# TIDA-01349_Inverter_VISense.net
KiCad netlist of a schematic drawn in Altium Designer
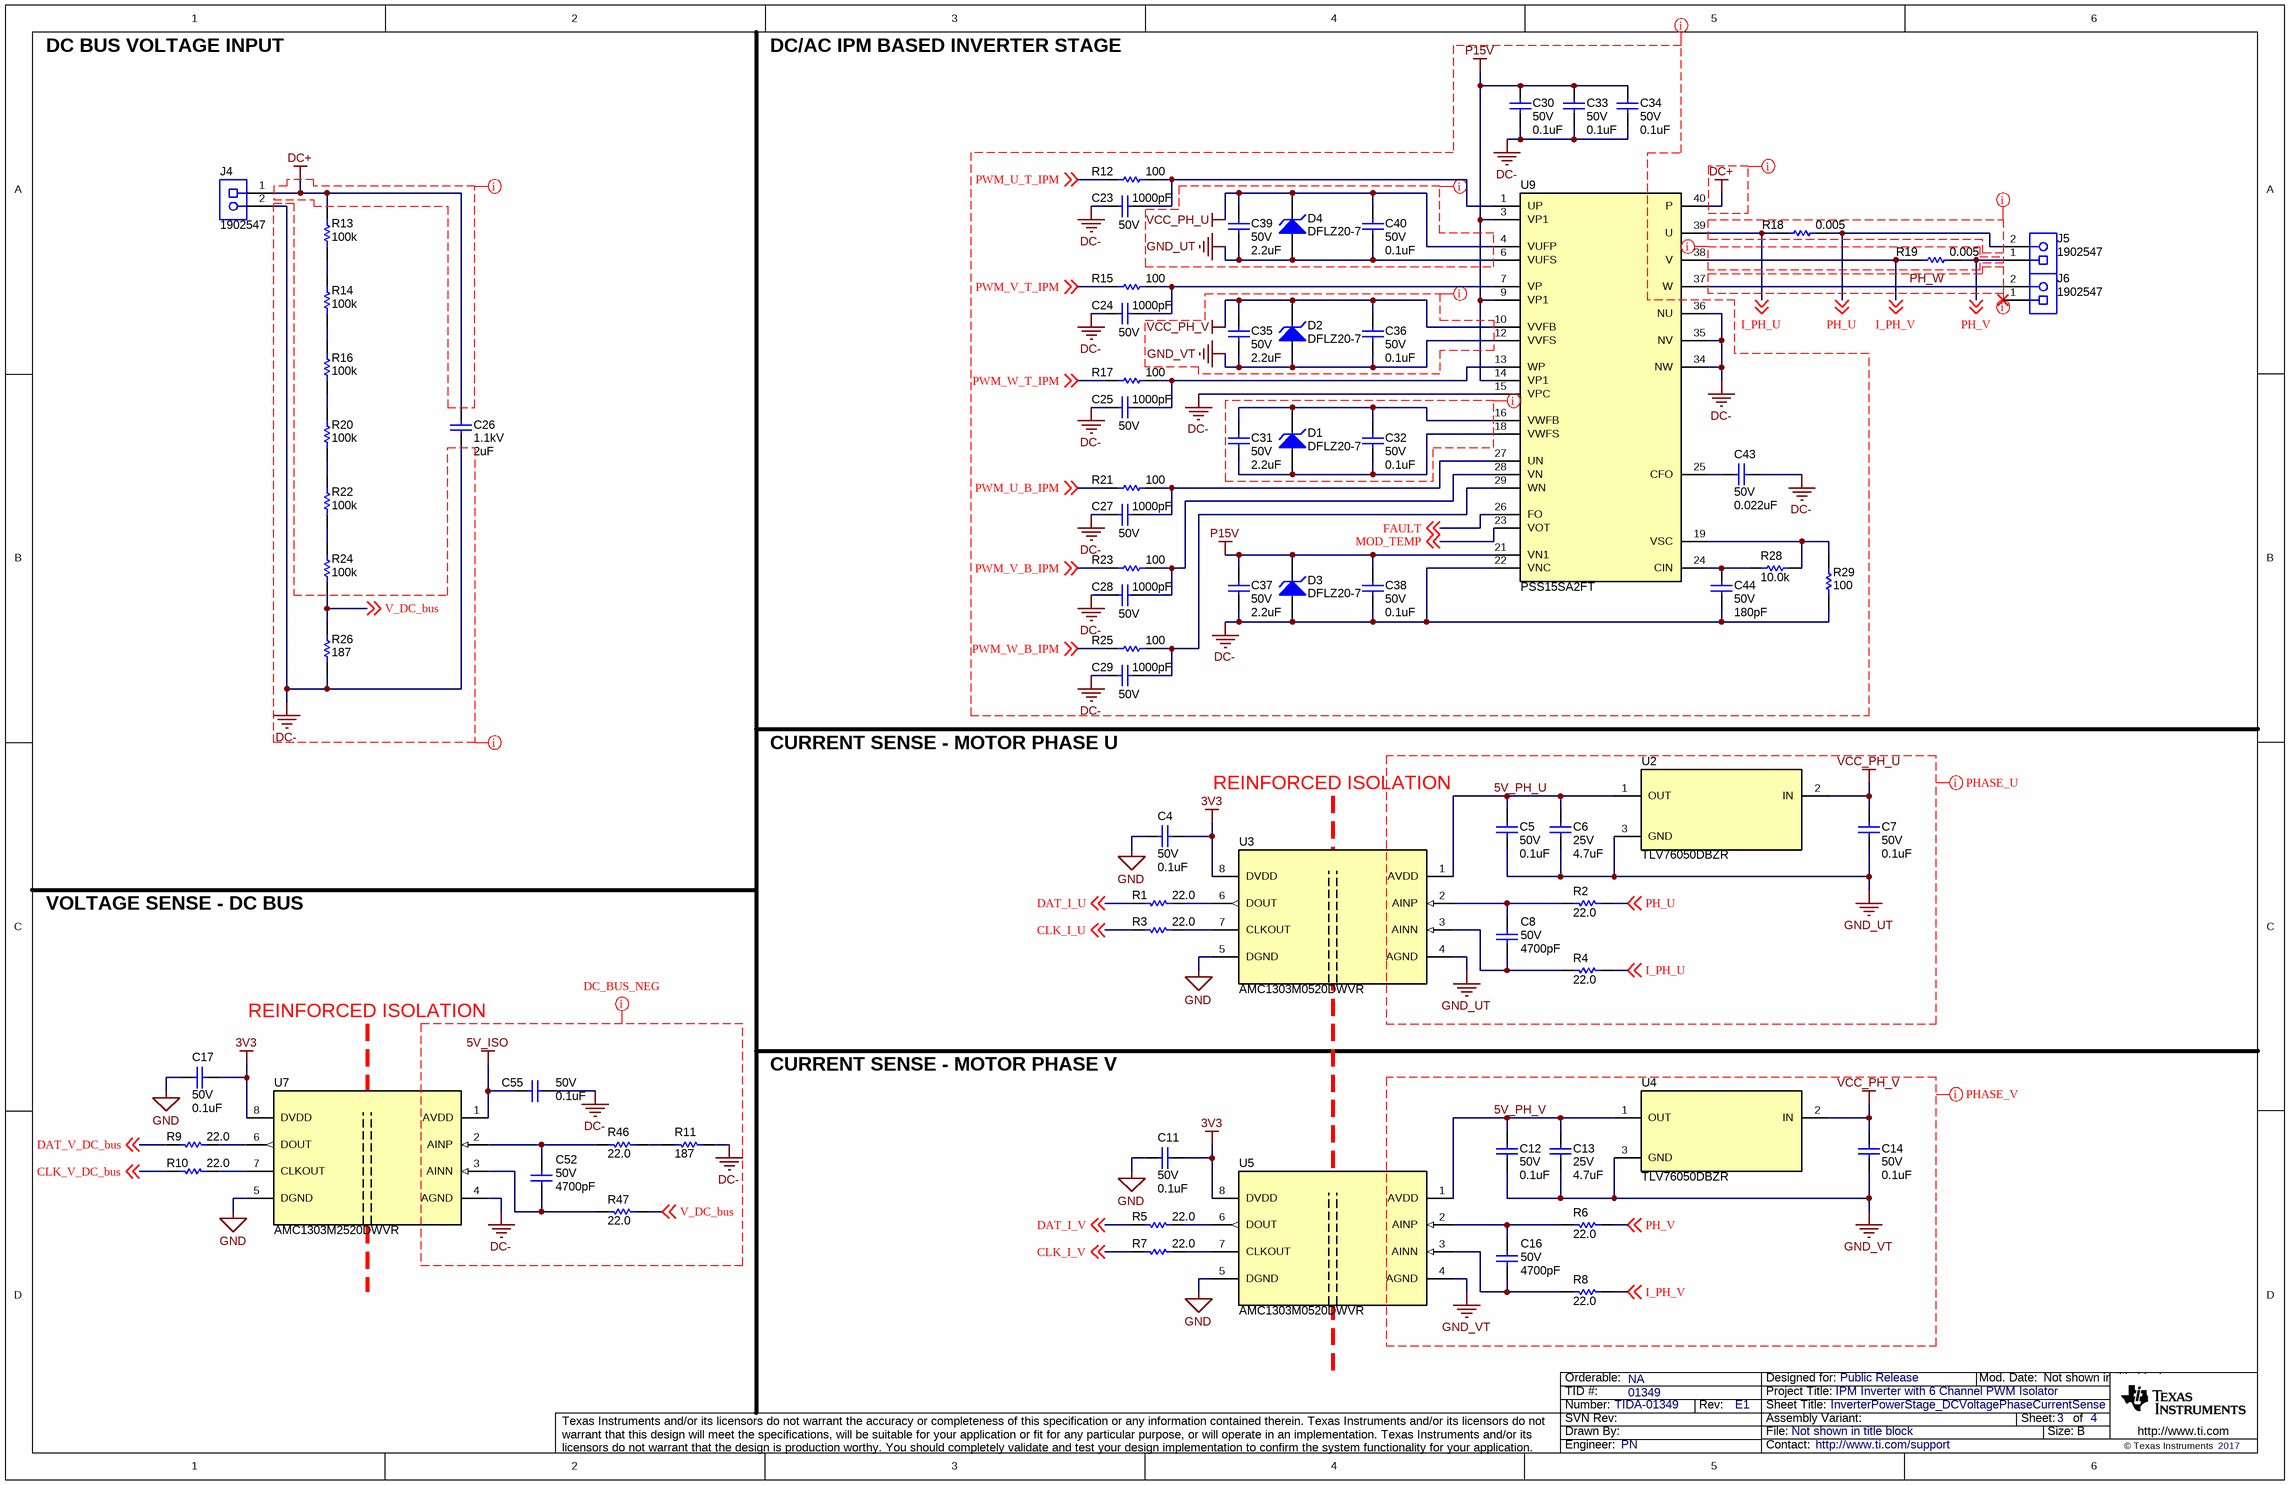
[diagram p0: TIDA-01349_Inverter_VISense.SchDoc]

(export (version "E")
  (design (tool "Eeschema 10.0.6"))
  (components
    (comp (ref "C4")
      (value "C0603C104K5RACTU")
      (footprint "0603")
      (description "CAP, CERM, 0.1 uF, 50 V, +/- 10%, X7R, 0603")
      (fields
        (field (name "MANUFACTURER") "Kemet")
        (field (name "VDC_V") "50V")
        (field (name "VALUEDISPLAYED") "0.1uF")
        (field (name "PUBLISHER") "Texas Instruments")
      )
      (libsource (lib "Altium Vault - TI") (part "Capacitor"))
    )
    (comp (ref "C5")
      (value "C1206C104K5RACTU")
      (footprint "1206")
      (description "CAP, CERM, 0.1 uF, 50 V, +/- 10%, X7R, 1206")
      (fields
        (field (name "MANUFACTURER") "Kemet")
        (field (name "VDC_V") "50V")
        (field (name "VALUEDISPLAYED") "0.1uF")
        (field (name "PUBLISHER") "Texas Instruments")
      )
      (libsource (lib "Altium Vault - TI") (part "Capacitor"))
    )
    (comp (ref "C6")
      (value "C2012X7R1E475K125AB")
      (footprint "0805_HV")
      (description "CAP, CERM, 4.7 uF, 25 V, +/- 10%, X7R, 0805")
      (fields
        (field (name "MANUFACTURER") "TDK")
        (field (name "VDC_V") "25V")
        (field (name "VALUEDISPLAYED") "4.7uF")
        (field (name "PUBLISHER") "Texas Instruments")
      )
      (libsource (lib "Altium Vault - TI") (part "Capacitor"))
    )
    (comp (ref "C7")
      (value "C0603C104K5RACTU")
      (footprint "0603")
      (description "CAP, CERM, 0.1 uF, 50 V, +/- 10%, X7R, 0603")
      (fields
        (field (name "MANUFACTURER") "Kemet")
        (field (name "VDC_V") "50V")
        (field (name "VALUEDISPLAYED") "0.1uF")
        (field (name "PUBLISHER") "Texas Instruments")
      )
      (libsource (lib "Altium Vault - TI") (part "Capacitor"))
    )
    (comp (ref "C8")
      (value "C0603C472K5RACTU")
      (footprint "0603")
      (description "CAP, CERM, 4700 pF, 50 V, +/- 10%, X7R, 0603")
      (fields
        (field (name "MANUFACTURER") "Kemet")
        (field (name "VDC_V") "50V")
        (field (name "VALUEDISPLAYED") "4700pF")
        (field (name "PUBLISHER") "Texas Instruments")
      )
      (libsource (lib "Altium Vault - TI") (part "Capacitor"))
    )
    (comp (ref "C11")
      (value "C0603C104K5RACTU")
      (footprint "0603")
      (description "CAP, CERM, 0.1 uF, 50 V, +/- 10%, X7R, 0603")
      (fields
        (field (name "MANUFACTURER") "Kemet")
        (field (name "VDC_V") "50V")
        (field (name "VALUEDISPLAYED") "0.1uF")
        (field (name "PUBLISHER") "Texas Instruments")
      )
      (libsource (lib "Altium Vault - TI") (part "Capacitor"))
    )
    (comp (ref "C12")
      (value "C1206C104K5RACTU")
      (footprint "1206")
      (description "CAP, CERM, 0.1 uF, 50 V, +/- 10%, X7R, 1206")
      (fields
        (field (name "MANUFACTURER") "Kemet")
        (field (name "VDC_V") "50V")
        (field (name "VALUEDISPLAYED") "0.1uF")
        (field (name "PUBLISHER") "Texas Instruments")
      )
      (libsource (lib "Altium Vault - TI") (part "Capacitor"))
    )
    (comp (ref "C13")
      (value "C2012X7R1E475K125AB")
      (footprint "0805_HV")
      (description "CAP, CERM, 4.7 uF, 25 V, +/- 10%, X7R, 0805")
      (fields
        (field (name "MANUFACTURER") "TDK")
        (field (name "VDC_V") "25V")
        (field (name "VALUEDISPLAYED") "4.7uF")
        (field (name "PUBLISHER") "Texas Instruments")
      )
      (libsource (lib "Altium Vault - TI") (part "Capacitor"))
    )
    (comp (ref "C14")
      (value "C0603C104K5RACTU")
      (footprint "0603")
      (description "CAP, CERM, 0.1 uF, 50 V, +/- 10%, X7R, 0603")
      (fields
        (field (name "MANUFACTURER") "Kemet")
        (field (name "VDC_V") "50V")
        (field (name "VALUEDISPLAYED") "0.1uF")
        (field (name "PUBLISHER") "Texas Instruments")
      )
      (libsource (lib "Altium Vault - TI") (part "Capacitor"))
    )
    (comp (ref "C16")
      (value "C0603C472K5RACTU")
      (footprint "0603")
      (description "CAP, CERM, 4700 pF, 50 V, +/- 10%, X7R, 0603")
      (fields
        (field (name "MANUFACTURER") "Kemet")
        (field (name "VDC_V") "50V")
        (field (name "VALUEDISPLAYED") "4700pF")
        (field (name "PUBLISHER") "Texas Instruments")
      )
      (libsource (lib "Altium Vault - TI") (part "Capacitor"))
    )
    (comp (ref "C17")
      (value "C0603C104K5RACTU")
      (footprint "0603")
      (description "CAP, CERM, 0.1 uF, 50 V, +/- 10%, X7R, 0603")
      (fields
        (field (name "MANUFACTURER") "Kemet")
        (field (name "VDC_V") "50V")
        (field (name "VALUEDISPLAYED") "0.1uF")
        (field (name "PUBLISHER") "Texas Instruments")
      )
      (libsource (lib "Altium Vault - TI") (part "Capacitor"))
    )
    (comp (ref "C23")
      (value "C0603C102J5GACTU")
      (footprint "0603")
      (description "CAP, CERM, 1000 pF, 50 V, +/- 5%, C0G/NP0, 0603")
      (fields
        (field (name "MANUFACTURER") "Kemet")
        (field (name "VDC_V") "50V")
        (field (name "VALUEDISPLAYED") "1000pF")
        (field (name "PUBLISHER") "Texas Instruments")
      )
      (libsource (lib "Altium Vault - TI") (part "Capacitor"))
    )
    (comp (ref "C24")
      (value "C0603C102J5GACTU")
      (footprint "0603")
      (description "CAP, CERM, 1000 pF, 50 V, +/- 5%, C0G/NP0, 0603")
      (fields
        (field (name "MANUFACTURER") "Kemet")
        (field (name "VDC_V") "50V")
        (field (name "VALUEDISPLAYED") "1000pF")
        (field (name "PUBLISHER") "Texas Instruments")
      )
      (libsource (lib "Altium Vault - TI") (part "Capacitor"))
    )
    (comp (ref "C25")
      (value "C0603C102J5GACTU")
      (footprint "0603")
      (description "CAP, CERM, 1000 pF, 50 V, +/- 5%, C0G/NP0, 0603")
      (fields
        (field (name "MANUFACTURER") "Kemet")
        (field (name "VDC_V") "50V")
        (field (name "VALUEDISPLAYED") "1000pF")
        (field (name "PUBLISHER") "Texas Instruments")
      )
      (libsource (lib "Altium Vault - TI") (part "Capacitor"))
    )
    (comp (ref "C26")
      (value "B32774D0205K000")
      (footprint "B32774_3150x2150x1250")
      (description "CAP, Film, 2 uF, 1100 V, +/- 10%, 0.011 ohm, TH")
      (fields
        (field (name "MANUFACTURER") "TDK")
        (field (name "VDC_V") "1.1kV")
        (field (name "VALUEDISPLAYED") "2uF")
        (field (name "PUBLISHER") "Texas Instruments")
      )
      (libsource (lib "Altium Vault - TI") (part "Capacitor"))
    )
    (comp (ref "C27")
      (value "C0603C102J5GACTU")
      (footprint "0603")
      (description "CAP, CERM, 1000 pF, 50 V, +/- 5%, C0G/NP0, 0603")
      (fields
        (field (name "MANUFACTURER") "Kemet")
        (field (name "VDC_V") "50V")
        (field (name "VALUEDISPLAYED") "1000pF")
        (field (name "PUBLISHER") "Texas Instruments")
      )
      (libsource (lib "Altium Vault - TI") (part "Capacitor"))
    )
    (comp (ref "C28")
      (value "C0603C102J5GACTU")
      (footprint "0603")
      (description "CAP, CERM, 1000 pF, 50 V, +/- 5%, C0G/NP0, 0603")
      (fields
        (field (name "MANUFACTURER") "Kemet")
        (field (name "VDC_V") "50V")
        (field (name "VALUEDISPLAYED") "1000pF")
        (field (name "PUBLISHER") "Texas Instruments")
      )
      (libsource (lib "Altium Vault - TI") (part "Capacitor"))
    )
    (comp (ref "C29")
      (value "C0603C102J5GACTU")
      (footprint "0603")
      (description "CAP, CERM, 1000 pF, 50 V, +/- 5%, C0G/NP0, 0603")
      (fields
        (field (name "MANUFACTURER") "Kemet")
        (field (name "VDC_V") "50V")
        (field (name "VALUEDISPLAYED") "1000pF")
        (field (name "PUBLISHER") "Texas Instruments")
      )
      (libsource (lib "Altium Vault - TI") (part "Capacitor"))
    )
    (comp (ref "C30")
      (value "C0603C104K5RACTU")
      (footprint "0603")
      (description "CAP, CERM, 0.1 uF, 50 V, +/- 10%, X7R, 0603")
      (fields
        (field (name "MANUFACTURER") "Kemet")
        (field (name "VDC_V") "50V")
        (field (name "VALUEDISPLAYED") "0.1uF")
        (field (name "PUBLISHER") "Texas Instruments")
      )
      (libsource (lib "Altium Vault - TI") (part "Capacitor"))
    )
    (comp (ref "C31")
      (value "UMK316B7225KL-T")
      (footprint "1206")
      (description "CAP, CERM, 2.2 uF, 50 V, +/- 10%, X7R, 1206")
      (fields
        (field (name "MANUFACTURER") "Taiyo Yuden")
        (field (name "VDC_V") "50V")
        (field (name "VALUEDISPLAYED") "2.2uF")
        (field (name "PUBLISHER") "Texas Instruments")
      )
      (libsource (lib "Altium Vault - TI") (part "Capacitor"))
    )
    (comp (ref "C32")
      (value "C0603C104K5RACTU")
      (footprint "0603")
      (description "CAP, CERM, 0.1 uF, 50 V, +/- 10%, X7R, 0603")
      (fields
        (field (name "MANUFACTURER") "Kemet")
        (field (name "VDC_V") "50V")
        (field (name "VALUEDISPLAYED") "0.1uF")
        (field (name "PUBLISHER") "Texas Instruments")
      )
      (libsource (lib "Altium Vault - TI") (part "Capacitor"))
    )
    (comp (ref "C33")
      (value "C0603C104K5RACTU")
      (footprint "0603")
      (description "CAP, CERM, 0.1 uF, 50 V, +/- 10%, X7R, 0603")
      (fields
        (field (name "MANUFACTURER") "Kemet")
        (field (name "VDC_V") "50V")
        (field (name "VALUEDISPLAYED") "0.1uF")
        (field (name "PUBLISHER") "Texas Instruments")
      )
      (libsource (lib "Altium Vault - TI") (part "Capacitor"))
    )
    (comp (ref "C34")
      (value "C0603C104K5RACTU")
      (footprint "0603")
      (description "CAP, CERM, 0.1 uF, 50 V, +/- 10%, X7R, 0603")
      (fields
        (field (name "MANUFACTURER") "Kemet")
        (field (name "VDC_V") "50V")
        (field (name "VALUEDISPLAYED") "0.1uF")
        (field (name "PUBLISHER") "Texas Instruments")
      )
      (libsource (lib "Altium Vault - TI") (part "Capacitor"))
    )
    (comp (ref "C35")
      (value "UMK316B7225KL-T")
      (footprint "1206")
      (description "CAP, CERM, 2.2 uF, 50 V, +/- 10%, X7R, 1206")
      (fields
        (field (name "MANUFACTURER") "Taiyo Yuden")
        (field (name "VDC_V") "50V")
        (field (name "VALUEDISPLAYED") "2.2uF")
        (field (name "PUBLISHER") "Texas Instruments")
      )
      (libsource (lib "Altium Vault - TI") (part "CMP-0009028-2"))
    )
    (comp (ref "C36")
      (value "C0603C104K5RACTU")
      (footprint "0603")
      (description "CAP, CERM, 0.1 uF, 50 V, +/- 10%, X7R, 0603")
      (fields
        (field (name "MANUFACTURER") "Kemet")
        (field (name "VDC_V") "50V")
        (field (name "VALUEDISPLAYED") "0.1uF")
        (field (name "PUBLISHER") "Texas Instruments")
      )
      (libsource (lib "Altium Vault - TI") (part "Capacitor"))
    )
    (comp (ref "C37")
      (value "UMK316B7225KL-T")
      (footprint "1206")
      (description "CAP, CERM, 2.2 uF, 50 V, +/- 10%, X7R, 1206")
      (fields
        (field (name "MANUFACTURER") "Taiyo Yuden")
        (field (name "VDC_V") "50V")
        (field (name "VALUEDISPLAYED") "2.2uF")
        (field (name "PUBLISHER") "Texas Instruments")
      )
      (libsource (lib "Altium Vault - TI") (part "Capacitor"))
    )
    (comp (ref "C38")
      (value "C0603C104K5RACTU")
      (footprint "0603")
      (description "CAP, CERM, 0.1 uF, 50 V, +/- 10%, X7R, 0603")
      (fields
        (field (name "MANUFACTURER") "Kemet")
        (field (name "VDC_V") "50V")
        (field (name "VALUEDISPLAYED") "0.1uF")
        (field (name "PUBLISHER") "Texas Instruments")
      )
      (libsource (lib "Altium Vault - TI") (part "Capacitor"))
    )
    (comp (ref "C39")
      (value "UMK316B7225KL-T")
      (footprint "1206")
      (description "CAP, CERM, 2.2 uF, 50 V, +/- 10%, X7R, 1206")
      (fields
        (field (name "MANUFACTURER") "Taiyo Yuden")
        (field (name "VDC_V") "50V")
        (field (name "VALUEDISPLAYED") "2.2uF")
        (field (name "PUBLISHER") "Texas Instruments")
      )
      (libsource (lib "Altium Vault - TI") (part "Capacitor"))
    )
    (comp (ref "C40")
      (value "C0603C104K5RACTU")
      (footprint "0603")
      (description "CAP, CERM, 0.1 uF, 50 V, +/- 10%, X7R, 0603")
      (fields
        (field (name "MANUFACTURER") "Kemet")
        (field (name "VDC_V") "50V")
        (field (name "VALUEDISPLAYED") "0.1uF")
        (field (name "PUBLISHER") "Texas Instruments")
      )
      (libsource (lib "Altium Vault - TI") (part "Capacitor"))
    )
    (comp (ref "C43")
      (value "C0603C223K5RACTU")
      (footprint "0603")
      (description "CAP, CERM, 0.022 uF, 50 V, +/- 10%, X7R, 0603")
      (fields
        (field (name "MANUFACTURER") "Kemet")
        (field (name "VDC_V") "50V")
        (field (name "VALUEDISPLAYED") "0.022uF")
        (field (name "PUBLISHER") "Texas Instruments")
      )
      (libsource (lib "Altium Vault - TI") (part "Capacitor"))
    )
    (comp (ref "C44")
      (value "C0603C181J5GACTU")
      (footprint "0603")
      (description "CAP, CERM, 180 pF, 50 V, +/- 5%, C0G/NP0, 0603")
      (fields
        (field (name "MANUFACTURER") "Kemet")
        (field (name "VDC_V") "50V")
        (field (name "VALUEDISPLAYED") "180pF")
        (field (name "PUBLISHER") "Texas Instruments")
      )
      (libsource (lib "Altium Vault - TI") (part "Capacitor"))
    )
    (comp (ref "C52")
      (value "C0603C472K5RACTU")
      (footprint "0603")
      (description "CAP, CERM, 4700 pF, 50 V, +/- 10%, X7R, 0603")
      (fields
        (field (name "MANUFACTURER") "Kemet")
        (field (name "VDC_V") "50V")
        (field (name "VALUEDISPLAYED") "4700pF")
        (field (name "PUBLISHER") "Texas Instruments")
      )
      (libsource (lib "Altium Vault - TI") (part "Capacitor"))
    )
    (comp (ref "C55")
      (value "C0603C104K5RACTU")
      (footprint "0603")
      (description "CAP, CERM, 0.1 uF, 50 V, +/- 10%, X7R, 0603")
      (fields
        (field (name "MANUFACTURER") "Kemet")
        (field (name "VDC_V") "50V")
        (field (name "VALUEDISPLAYED") "0.1uF")
        (field (name "PUBLISHER") "Texas Instruments")
      )
      (libsource (lib "Altium Vault - TI") (part "Capacitor"))
    )
    (comp (ref "D1")
      (value "DFLZ20-7")
      (footprint "PowerDI123")
      (description "Diode, Zener, 20 V, 1 W, PowerDI123")
      (fields (field (name "MANUFACTURER") "Diodes Inc.") (field (name "PUBLISHER") "Texas Instruments"))
      (libsource (lib "Altium Vault - TI") (part "Zener"))
    )
    (comp (ref "D2")
      (value "DFLZ20-7")
      (footprint "PowerDI123")
      (description "Diode, Zener, 20 V, 1 W, PowerDI123")
      (fields (field (name "MANUFACTURER") "Diodes Inc.") (field (name "PUBLISHER") "Texas Instruments"))
      (libsource (lib "Altium Vault - TI") (part "Zener"))
    )
    (comp (ref "D3")
      (value "DFLZ20-7")
      (footprint "PowerDI123")
      (description "Diode, Zener, 20 V, 1 W, PowerDI123")
      (fields (field (name "MANUFACTURER") "Diodes Inc.") (field (name "PUBLISHER") "Texas Instruments"))
      (libsource (lib "Altium Vault - TI") (part "Zener"))
    )
    (comp (ref "D4")
      (value "DFLZ20-7")
      (footprint "PowerDI123")
      (description "Diode, Zener, 20 V, 1 W, PowerDI123")
      (fields (field (name "MANUFACTURER") "Diodes Inc.") (field (name "PUBLISHER") "Texas Instruments"))
      (libsource (lib "Altium Vault - TI") (part "Zener"))
    )
    (comp (ref "J4")
      (value "1902547")
      (footprint "Phoenix_1902547")
      (description "Terminal Block, 9.52mm, 2x1, R/A, TH")
      (fields (field (name "MANUFACTURER") "Phoenix Contact") (field (name "PUBLISHER") "Texas Instruments"))
      (libsource (lib "") (part "Receptacle_2x1_1"))
    )
    (comp (ref "J5")
      (value "1902547")
      (footprint "Phoenix_1902547")
      (description "Terminal Block, 9.52mm, 2x1, R/A, TH")
      (fields (field (name "MANUFACTURER") "Phoenix Contact") (field (name "PUBLISHER") "Texas Instruments"))
      (libsource (lib "Altium Vault - TI") (part "Receptacle_2x1"))
    )
    (comp (ref "J6")
      (value "1902547")
      (footprint "Phoenix_1902547")
      (description "Terminal Block, 9.52mm, 2x1, R/A, TH")
      (fields (field (name "MANUFACTURER") "Phoenix Contact") (field (name "PUBLISHER") "Texas Instruments"))
      (libsource (lib "Altium Vault - TI") (part "Receptacle_2x1"))
    )
    (comp (ref "R1")
      (value "RC0603FR-0722RL")
      (footprint "0603")
      (description "RES, 22.0, 1%, 0.1 W, 0603")
      (fields
        (field (name "MANUFACTURER") "Yageo America")
        (field (name "VALUEDISPLAYED") "22.0")
        (field (name "PUBLISHER") "Texas Instruments")
      )
      (libsource (lib "Altium Vault - TI") (part "Resistor"))
    )
    (comp (ref "R2")
      (value "RC0603FR-0722RL")
      (footprint "0603")
      (description "RES, 22.0, 1%, 0.1 W, 0603")
      (fields
        (field (name "MANUFACTURER") "Yageo America")
        (field (name "VALUEDISPLAYED") "22.0")
        (field (name "PUBLISHER") "Texas Instruments")
      )
      (libsource (lib "Altium Vault - TI") (part "Resistor"))
    )
    (comp (ref "R3")
      (value "RC0603FR-0722RL")
      (footprint "0603")
      (description "RES, 22.0, 1%, 0.1 W, 0603")
      (fields
        (field (name "MANUFACTURER") "Yageo America")
        (field (name "VALUEDISPLAYED") "22.0")
        (field (name "PUBLISHER") "Texas Instruments")
      )
      (libsource (lib "Altium Vault - TI") (part "Resistor"))
    )
    (comp (ref "R4")
      (value "RC0603FR-0722RL")
      (footprint "0603")
      (description "RES, 22.0, 1%, 0.1 W, 0603")
      (fields
        (field (name "MANUFACTURER") "Yageo America")
        (field (name "VALUEDISPLAYED") "22.0")
        (field (name "PUBLISHER") "Texas Instruments")
      )
      (libsource (lib "Altium Vault - TI") (part "Resistor"))
    )
    (comp (ref "R5")
      (value "RC0603FR-0722RL")
      (footprint "0603")
      (description "RES, 22.0, 1%, 0.1 W, 0603")
      (fields
        (field (name "MANUFACTURER") "Yageo America")
        (field (name "VALUEDISPLAYED") "22.0")
        (field (name "PUBLISHER") "Texas Instruments")
      )
      (libsource (lib "Altium Vault - TI") (part "Resistor"))
    )
    (comp (ref "R6")
      (value "RC0603FR-0722RL")
      (footprint "0603")
      (description "RES, 22.0, 1%, 0.1 W, 0603")
      (fields
        (field (name "MANUFACTURER") "Yageo America")
        (field (name "VALUEDISPLAYED") "22.0")
        (field (name "PUBLISHER") "Texas Instruments")
      )
      (libsource (lib "Altium Vault - TI") (part "Resistor"))
    )
    (comp (ref "R7")
      (value "RC0603FR-0722RL")
      (footprint "0603")
      (description "RES, 22.0, 1%, 0.1 W, 0603")
      (fields
        (field (name "MANUFACTURER") "Yageo America")
        (field (name "VALUEDISPLAYED") "22.0")
        (field (name "PUBLISHER") "Texas Instruments")
      )
      (libsource (lib "Altium Vault - TI") (part "Resistor"))
    )
    (comp (ref "R8")
      (value "RC0603FR-0722RL")
      (footprint "0603")
      (description "RES, 22.0, 1%, 0.1 W, 0603")
      (fields
        (field (name "MANUFACTURER") "Yageo America")
        (field (name "VALUEDISPLAYED") "22.0")
        (field (name "PUBLISHER") "Texas Instruments")
      )
      (libsource (lib "Altium Vault - TI") (part "Resistor"))
    )
    (comp (ref "R9")
      (value "RC0603FR-0722RL")
      (footprint "0603")
      (description "RES, 22.0, 1%, 0.1 W, 0603")
      (fields
        (field (name "MANUFACTURER") "Yageo America")
        (field (name "VALUEDISPLAYED") "22.0")
        (field (name "PUBLISHER") "Texas Instruments")
      )
      (libsource (lib "Altium Vault - TI") (part "Resistor"))
    )
    (comp (ref "R10")
      (value "RC0603FR-0722RL")
      (footprint "0603")
      (description "RES, 22.0, 1%, 0.1 W, 0603")
      (fields
        (field (name "MANUFACTURER") "Yageo America")
        (field (name "VALUEDISPLAYED") "22.0")
        (field (name "PUBLISHER") "Texas Instruments")
      )
      (libsource (lib "Altium Vault - TI") (part "Resistor"))
    )
    (comp (ref "R11")
      (value "CRCW0603187RFKEA")
      (footprint "0603")
      (description "RES, 187, 1%, 0.1 W, 0603")
      (fields
        (field (name "MANUFACTURER") "Vishay-Dale")
        (field (name "VALUEDISPLAYED") "187")
        (field (name "PUBLISHER") "Texas Instruments")
      )
      (libsource (lib "Altium Vault - TI") (part "Resistor"))
    )
    (comp (ref "R12")
      (value "CRCW0603100RFKEA")
      (footprint "0603")
      (description "RES, 100, 1%, 0.1 W, 0603")
      (fields
        (field (name "MANUFACTURER") "Vishay-Dale")
        (field (name "VALUEDISPLAYED") "100")
        (field (name "PUBLISHER") "Texas Instruments")
      )
      (libsource (lib "Altium Vault - TI") (part "Resistor"))
    )
    (comp (ref "R13")
      (value "CRCW1206100KFKEA")
      (footprint "1206")
      (description "RES, 100 k, 1%, 0.25 W, 1206")
      (fields
        (field (name "MANUFACTURER") "Vishay-Dale")
        (field (name "VALUEDISPLAYED") "100k")
        (field (name "PUBLISHER") "Texas Instruments")
      )
      (libsource (lib "Altium Vault - TI") (part "Resistor"))
    )
    (comp (ref "R14")
      (value "CRCW1206100KFKEA")
      (footprint "1206")
      (description "RES, 100 k, 1%, 0.25 W, 1206")
      (fields
        (field (name "MANUFACTURER") "Vishay-Dale")
        (field (name "VALUEDISPLAYED") "100k")
        (field (name "PUBLISHER") "Texas Instruments")
      )
      (libsource (lib "Altium Vault - TI") (part "Resistor"))
    )
    (comp (ref "R15")
      (value "CRCW0603100RFKEA")
      (footprint "0603")
      (description "RES, 100, 1%, 0.1 W, 0603")
      (fields
        (field (name "MANUFACTURER") "Vishay-Dale")
        (field (name "VALUEDISPLAYED") "100")
        (field (name "PUBLISHER") "Texas Instruments")
      )
      (libsource (lib "Altium Vault - TI") (part "Resistor"))
    )
    (comp (ref "R16")
      (value "CRCW1206100KFKEA")
      (footprint "1206")
      (description "RES, 100 k, 1%, 0.25 W, 1206")
      (fields
        (field (name "MANUFACTURER") "Vishay-Dale")
        (field (name "VALUEDISPLAYED") "100k")
        (field (name "PUBLISHER") "Texas Instruments")
      )
      (libsource (lib "Altium Vault - TI") (part "Resistor"))
    )
    (comp (ref "R17")
      (value "CRCW0603100RFKEA")
      (footprint "0603")
      (description "RES, 100, 1%, 0.1 W, 0603")
      (fields
        (field (name "MANUFACTURER") "Vishay-Dale")
        (field (name "VALUEDISPLAYED") "100")
        (field (name "PUBLISHER") "Texas Instruments")
      )
      (libsource (lib "Altium Vault - TI") (part "Resistor"))
    )
    (comp (ref "R18")
      (value "CSNL1206FT5L00")
      (footprint "CSNL1206")
      (description "RES, 0.005, 1%, 1 W, 1206")
      (fields
        (field (name "MANUFACTURER") "Stackpole Electronics Inc")
        (field (name "VALUEDISPLAYED") "0.005")
        (field (name "PUBLISHER") "Texas Instruments")
      )
      (libsource (lib "Altium Vault - TI") (part "Resistor"))
    )
    (comp (ref "R19")
      (value "CSNL1206FT5L00")
      (footprint "CSNL1206")
      (description "RES, 0.005, 1%, 1 W, 1206")
      (fields
        (field (name "MANUFACTURER") "Stackpole Electronics Inc")
        (field (name "VALUEDISPLAYED") "0.005")
        (field (name "PUBLISHER") "Texas Instruments")
      )
      (libsource (lib "Altium Vault - TI") (part "Resistor"))
    )
    (comp (ref "R20")
      (value "CRCW1206100KFKEA")
      (footprint "1206")
      (description "RES, 100 k, 1%, 0.25 W, 1206")
      (fields
        (field (name "MANUFACTURER") "Vishay-Dale")
        (field (name "VALUEDISPLAYED") "100k")
        (field (name "PUBLISHER") "Texas Instruments")
      )
      (libsource (lib "Altium Vault - TI") (part "Resistor"))
    )
    (comp (ref "R21")
      (value "CRCW0603100RFKEA")
      (footprint "0603")
      (description "RES, 100, 1%, 0.1 W, 0603")
      (fields
        (field (name "MANUFACTURER") "Vishay-Dale")
        (field (name "VALUEDISPLAYED") "100")
        (field (name "PUBLISHER") "Texas Instruments")
      )
      (libsource (lib "Altium Vault - TI") (part "Resistor"))
    )
    (comp (ref "R22")
      (value "CRCW1206100KFKEA")
      (footprint "1206")
      (description "RES, 100 k, 1%, 0.25 W, 1206")
      (fields
        (field (name "MANUFACTURER") "Vishay-Dale")
        (field (name "VALUEDISPLAYED") "100k")
        (field (name "PUBLISHER") "Texas Instruments")
      )
      (libsource (lib "Altium Vault - TI") (part "Resistor"))
    )
    (comp (ref "R23")
      (value "CRCW0603100RFKEA")
      (footprint "0603")
      (description "RES, 100, 1%, 0.1 W, 0603")
      (fields
        (field (name "MANUFACTURER") "Vishay-Dale")
        (field (name "VALUEDISPLAYED") "100")
        (field (name "PUBLISHER") "Texas Instruments")
      )
      (libsource (lib "Altium Vault - TI") (part "Resistor"))
    )
    (comp (ref "R24")
      (value "CRCW1206100KFKEA")
      (footprint "1206")
      (description "RES, 100 k, 1%, 0.25 W, 1206")
      (fields
        (field (name "MANUFACTURER") "Vishay-Dale")
        (field (name "VALUEDISPLAYED") "100k")
        (field (name "PUBLISHER") "Texas Instruments")
      )
      (libsource (lib "Altium Vault - TI") (part "Resistor"))
    )
    (comp (ref "R25")
      (value "CRCW0603100RFKEA")
      (footprint "0603")
      (description "RES, 100, 1%, 0.1 W, 0603")
      (fields
        (field (name "MANUFACTURER") "Vishay-Dale")
        (field (name "VALUEDISPLAYED") "100")
        (field (name "PUBLISHER") "Texas Instruments")
      )
      (libsource (lib "Altium Vault - TI") (part "Resistor"))
    )
    (comp (ref "R26")
      (value "CRCW0603187RFKEA")
      (footprint "0603")
      (description "RES, 187, 1%, 0.1 W, 0603")
      (fields
        (field (name "MANUFACTURER") "Vishay-Dale")
        (field (name "VALUEDISPLAYED") "187")
        (field (name "PUBLISHER") "Texas Instruments")
      )
      (libsource (lib "Altium Vault - TI") (part "Resistor"))
    )
    (comp (ref "R28")
      (value "CRCW060310K0FKEA")
      (footprint "0603")
      (description "RES, 10.0 k, 1%, 0.1 W, 0603")
      (fields
        (field (name "MANUFACTURER") "Vishay-Dale")
        (field (name "VALUEDISPLAYED") "10.0k")
        (field (name "PUBLISHER") "Texas Instruments")
      )
      (libsource (lib "Altium Vault - TI") (part "Resistor"))
    )
    (comp (ref "R29")
      (value "CRCW0603100RFKEA")
      (footprint "0603")
      (description "RES, 100, 1%, 0.1 W, 0603")
      (fields
        (field (name "MANUFACTURER") "Vishay-Dale")
        (field (name "VALUEDISPLAYED") "100")
        (field (name "PUBLISHER") "Texas Instruments")
      )
      (libsource (lib "Altium Vault - TI") (part "Resistor"))
    )
    (comp (ref "R46")
      (value "RC0603FR-0722RL")
      (footprint "0603")
      (description "RES, 22.0, 1%, 0.1 W, 0603")
      (fields
        (field (name "MANUFACTURER") "Yageo America")
        (field (name "VALUEDISPLAYED") "22.0")
        (field (name "PUBLISHER") "Texas Instruments")
      )
      (libsource (lib "Altium Vault - TI") (part "Resistor"))
    )
    (comp (ref "R47")
      (value "RC0603FR-0722RL")
      (footprint "0603")
      (description "RES, 22.0, 1%, 0.1 W, 0603")
      (fields
        (field (name "MANUFACTURER") "Yageo America")
        (field (name "VALUEDISPLAYED") "22.0")
        (field (name "PUBLISHER") "Texas Instruments")
      )
      (libsource (lib "Altium Vault - TI") (part "Resistor"))
    )
    (comp (ref "U2")
      (value "TLV76050DBZR")
      (footprint "DBZ0003A_N")
      (description "100-mA, 30-V, Fixed-Output, Linear-Voltage Regulator, DBZ0003A (SOT-23-3)")
      (fields
        (field (name "ALTERNATE PARTNUMBER") "TLV76050DBZT")
        (field (name "MANUFACTURER") "Texas Instruments")
        (field (name "PARTNUMBER") "TLV76050DBZR")
      )
      (libsource (lib "Altium Vault - TI") (part "TLV760xx"))
    )
    (comp (ref "U3")
      (value "AMC1303M0520DWVR")
      (footprint "DWV0008A")
      (fields
        (field (name "ALTERNATE PARTNUMBER") "AMC1303M0520DWV")
        (field (name "MANUFACTURER") "Texas Instruments")
        (field (name "PARTNUMBER") "AMC1303M0520DWVR")
      )
      (libsource (lib "Altium Vault - TI") (part "AMC1303M"))
    )
    (comp (ref "U4")
      (value "TLV76050DBZR")
      (footprint "DBZ0003A_N")
      (description "100-mA, 30-V, Fixed-Output, Linear-Voltage Regulator, DBZ0003A (SOT-23-3)")
      (fields
        (field (name "ALTERNATE PARTNUMBER") "TLV76050DBZT")
        (field (name "MANUFACTURER") "Texas Instruments")
        (field (name "PARTNUMBER") "TLV76050DBZR")
      )
      (libsource (lib "Altium Vault - TI") (part "TLV760xx"))
    )
    (comp (ref "U5")
      (value "AMC1303M0520DWVR")
      (footprint "DWV0008A")
      (fields
        (field (name "ALTERNATE PARTNUMBER") "AMC1303M0520DWV")
        (field (name "MANUFACTURER") "Texas Instruments")
        (field (name "PARTNUMBER") "AMC1303M0520DWVR")
      )
      (libsource (lib "Altium Vault - TI") (part "AMC1303M"))
    )
    (comp (ref "U7")
      (value "AMC1303M2520DWVR")
      (footprint "DWV0008A")
      (fields
        (field (name "ALTERNATE PARTNUMBER") "AMC1303M2520DWV")
        (field (name "MANUFACTURER") "Texas Instruments")
        (field (name "PARTNUMBER") "AMC1303M2520DWVR")
      )
      (libsource (lib "Altium Vault - TI") (part "AMC1303M"))
    )
    (comp (ref "U9")
      (value "PSS15SA2FT")
      (footprint "PSS15SA2FT")
      (description "Dual-In-Line Package Intelligent Power Module, TH")
      (fields (field (name "MANUFACTURER") "Mitsubishi") (field (name "PUBLISHER") "Texas Instruments"))
      (libsource (lib "Altium Vault - TI") (part "CMP-0077821-1"))
    )
  )
  (nets
    (net (code "1") (name "/5V_PH_U") (class "Default")
      (node (ref "C5") (pin "2") (pinfunction "2_2") (pintype "passive"))
      (node (ref "C6") (pin "1") (pinfunction "1_1") (pintype "passive"))
      (node (ref "U2") (pin "1") (pinfunction "OUT_1") (pintype "power_in"))
      (node (ref "U3") (pin "1") (pinfunction "AVDD_1") (pintype "power_in"))
    )
    (net (code "2") (name "/5V_PH_V") (class "Default")
      (node (ref "C12") (pin "2") (pinfunction "2_2") (pintype "passive"))
      (node (ref "C13") (pin "1") (pinfunction "1_1") (pintype "passive"))
      (node (ref "U4") (pin "1") (pinfunction "OUT_1") (pintype "power_in"))
      (node (ref "U5") (pin "1") (pinfunction "AVDD_1") (pintype "power_in"))
    )
    (net (code "3") (name "/PH_W") (class "Default")
      (node (ref "J6") (pin "2") (pinfunction "2_2") (pintype "passive"))
      (node (ref "U9") (pin "37") (pinfunction "W_37") (pintype "passive"))
    )
    (net (code "4") (name "3V3") (class "Default")
      (node (ref "C11") (pin "1") (pinfunction "1_1") (pintype "passive"))
      (node (ref "C17") (pin "1") (pinfunction "1_1") (pintype "passive"))
      (node (ref "C4") (pin "1") (pinfunction "1_1") (pintype "passive"))
      (node (ref "U3") (pin "8") (pinfunction "DVDD_8") (pintype "power_in"))
      (node (ref "U5") (pin "8") (pinfunction "DVDD_8") (pintype "power_in"))
      (node (ref "U7") (pin "8") (pinfunction "DVDD_8") (pintype "power_in"))
    )
    (net (code "5") (name "5V_ISO") (class "Default")
      (node (ref "C55") (pin "2") (pinfunction "2_2") (pintype "passive"))
      (node (ref "U7") (pin "1") (pinfunction "AVDD_1") (pintype "power_in"))
    )
    (net (code "6") (name "CLK_I_U") (class "Default")
      (node (ref "R3") (pin "2") (pinfunction "2_2") (pintype "passive"))
    )
    (net (code "7") (name "CLK_I_V") (class "Default")
      (node (ref "R7") (pin "2") (pinfunction "2_2") (pintype "passive"))
    )
    (net (code "8") (name "CLK_V_DC_bus") (class "Default")
      (node (ref "R10") (pin "2") (pinfunction "2_2") (pintype "passive"))
    )
    (net (code "9") (name "DAT_I_U") (class "Default")
      (node (ref "R1") (pin "2") (pinfunction "2_2") (pintype "passive"))
    )
    (net (code "10") (name "DAT_I_V") (class "Default")
      (node (ref "R5") (pin "2") (pinfunction "2_2") (pintype "passive"))
    )
    (net (code "11") (name "DAT_V_DC_bus") (class "Default")
      (node (ref "R9") (pin "2") (pinfunction "2_2") (pintype "passive"))
    )
    (net (code "12") (name "DC+") (class "Default")
      (node (ref "C26") (pin "1") (pinfunction "1_1") (pintype "passive"))
      (node (ref "J4") (pin "1") (pinfunction "1_1") (pintype "passive"))
      (node (ref "R13") (pin "2") (pinfunction "2_2") (pintype "passive"))
      (node (ref "U9") (pin "40") (pinfunction "P_40") (pintype "passive"))
    )
    (net (code "13") (name "DC-") (class "Default")
      (node (ref "C23") (pin "2") (pinfunction "2_2") (pintype "passive"))
      (node (ref "C24") (pin "2") (pinfunction "2_2") (pintype "passive"))
      (node (ref "C25") (pin "2") (pinfunction "2_2") (pintype "passive"))
      (node (ref "C26") (pin "2") (pinfunction "2_2") (pintype "passive"))
      (node (ref "C27") (pin "2") (pinfunction "2_2") (pintype "passive"))
      (node (ref "C28") (pin "2") (pinfunction "2_2") (pintype "passive"))
      (node (ref "C29") (pin "2") (pinfunction "2_2") (pintype "passive"))
      (node (ref "C30") (pin "2") (pinfunction "2_2") (pintype "passive"))
      (node (ref "C33") (pin "2") (pinfunction "2_2") (pintype "passive"))
      (node (ref "C34") (pin "2") (pinfunction "2_2") (pintype "passive"))
      (node (ref "C37") (pin "2") (pinfunction "2_2") (pintype "passive"))
      (node (ref "C38") (pin "2") (pinfunction "2_2") (pintype "passive"))
      (node (ref "C43") (pin "1") (pinfunction "1_1") (pintype "passive"))
      (node (ref "C44") (pin "2") (pinfunction "2_2") (pintype "passive"))
      (node (ref "C55") (pin "1") (pinfunction "1_1") (pintype "passive"))
      (node (ref "D3") (pin "2") (pinfunction "A_2") (pintype "passive"))
      (node (ref "J4") (pin "2") (pinfunction "2_2") (pintype "passive"))
      (node (ref "R11") (pin "1") (pinfunction "1_1") (pintype "passive"))
      (node (ref "R26") (pin "1") (pinfunction "1_1") (pintype "passive"))
      (node (ref "R29") (pin "2") (pinfunction "2_2") (pintype "passive"))
      (node (ref "U7") (pin "4") (pinfunction "AGND_4") (pintype "power_in"))
      (node (ref "U9") (pin "15") (pinfunction "VPC_15") (pintype "passive"))
      (node (ref "U9") (pin "22") (pinfunction "VNC_22") (pintype "passive"))
      (node (ref "U9") (pin "34") (pinfunction "NW_34") (pintype "passive"))
      (node (ref "U9") (pin "35") (pinfunction "NV_35") (pintype "passive"))
      (node (ref "U9") (pin "36") (pinfunction "NU_36") (pintype "passive"))
    )
    (net (code "14") (name "FAULT") (class "Default")
      (node (ref "U9") (pin "26") (pinfunction "FO_26") (pintype "passive"))
    )
    (net (code "15") (name "GND") (class "Default")
      (node (ref "C11") (pin "2") (pinfunction "2_2") (pintype "passive"))
      (node (ref "C17") (pin "2") (pinfunction "2_2") (pintype "passive"))
      (node (ref "C4") (pin "2") (pinfunction "2_2") (pintype "passive"))
      (node (ref "U3") (pin "5") (pinfunction "DGND_5") (pintype "power_in"))
      (node (ref "U5") (pin "5") (pinfunction "DGND_5") (pintype "power_in"))
      (node (ref "U7") (pin "5") (pinfunction "DGND_5") (pintype "power_in"))
    )
    (net (code "16") (name "GND_UT") (class "Default")
      (node (ref "C39") (pin "2") (pinfunction "2_2") (pintype "passive"))
      (node (ref "C40") (pin "2") (pinfunction "2_2") (pintype "passive"))
      (node (ref "C5") (pin "1") (pinfunction "1_1") (pintype "passive"))
      (node (ref "C6") (pin "2") (pinfunction "2_2") (pintype "passive"))
      (node (ref "C7") (pin "1") (pinfunction "1_1") (pintype "passive"))
      (node (ref "D4") (pin "2") (pinfunction "A_2") (pintype "passive"))
      (node (ref "U2") (pin "3") (pinfunction "GND_3") (pintype "power_in"))
      (node (ref "U3") (pin "4") (pinfunction "AGND_4") (pintype "power_in"))
      (node (ref "U9") (pin "6") (pinfunction "VUFS_6") (pintype "passive"))
    )
    (net (code "17") (name "GND_VT") (class "Default")
      (node (ref "C12") (pin "1") (pinfunction "1_1") (pintype "passive"))
      (node (ref "C13") (pin "2") (pinfunction "2_2") (pintype "passive"))
      (node (ref "C14") (pin "1") (pinfunction "1_1") (pintype "passive"))
      (node (ref "C35") (pin "2") (pinfunction "2_2") (pintype "passive"))
      (node (ref "C36") (pin "2") (pinfunction "2_2") (pintype "passive"))
      (node (ref "D2") (pin "2") (pinfunction "A_2") (pintype "passive"))
      (node (ref "U4") (pin "3") (pinfunction "GND_3") (pintype "power_in"))
      (node (ref "U5") (pin "4") (pinfunction "AGND_4") (pintype "power_in"))
      (node (ref "U9") (pin "12") (pinfunction "VVFS_12") (pintype "passive"))
    )
    (net (code "18") (name "I_PH_U") (class "Default")
      (node (ref "R18") (pin "1") (pinfunction "1_1") (pintype "passive"))
      (node (ref "R4") (pin "1") (pinfunction "1_1") (pintype "passive"))
      (node (ref "U9") (pin "39") (pinfunction "U_39") (pintype "passive"))
    )
    (net (code "19") (name "I_PH_V") (class "Default")
      (node (ref "R19") (pin "1") (pinfunction "1_1") (pintype "passive"))
      (node (ref "R8") (pin "1") (pinfunction "1_1") (pintype "passive"))
      (node (ref "U9") (pin "38") (pinfunction "V_38") (pintype "passive"))
    )
    (net (code "20") (name "MOD_TEMP") (class "Default")
      (node (ref "U9") (pin "23") (pinfunction "VOT_23") (pintype "passive"))
    )
    (net (code "21") (name "Net-(D1-A)") (class "Default")
      (node (ref "C31") (pin "2") (pinfunction "2_2") (pintype "passive"))
      (node (ref "C32") (pin "2") (pinfunction "2_2") (pintype "passive"))
      (node (ref "D1") (pin "2") (pinfunction "A_2") (pintype "passive"))
      (node (ref "U9") (pin "18") (pinfunction "VWFS_18") (pintype "passive"))
    )
    (net (code "22") (name "Net-(D1-K)") (class "Default")
      (node (ref "C31") (pin "1") (pinfunction "1_1") (pintype "passive"))
      (node (ref "C32") (pin "1") (pinfunction "1_1") (pintype "passive"))
      (node (ref "D1") (pin "1") (pinfunction "K_1") (pintype "passive"))
      (node (ref "U9") (pin "16") (pinfunction "VWFB_16") (pintype "passive"))
    )
    (net (code "23") (name "Net-(R11-Pad2)") (class "Default")
      (node (ref "R11") (pin "2") (pinfunction "2_2") (pintype "passive"))
      (node (ref "R46") (pin "1") (pinfunction "1_1") (pintype "passive"))
    )
    (net (code "24") (name "Net-(R13-Pad1)") (class "Default")
      (node (ref "R13") (pin "1") (pinfunction "1_1") (pintype "passive"))
      (node (ref "R14") (pin "2") (pinfunction "2_2") (pintype "passive"))
    )
    (net (code "25") (name "Net-(R14-Pad1)") (class "Default")
      (node (ref "R14") (pin "1") (pinfunction "1_1") (pintype "passive"))
      (node (ref "R16") (pin "2") (pinfunction "2_2") (pintype "passive"))
    )
    (net (code "26") (name "Net-(R16-Pad1)") (class "Default")
      (node (ref "R16") (pin "1") (pinfunction "1_1") (pintype "passive"))
      (node (ref "R20") (pin "2") (pinfunction "2_2") (pintype "passive"))
    )
    (net (code "27") (name "Net-(R20-Pad1)") (class "Default")
      (node (ref "R20") (pin "1") (pinfunction "1_1") (pintype "passive"))
      (node (ref "R22") (pin "2") (pinfunction "2_2") (pintype "passive"))
    )
    (net (code "28") (name "Net-(R22-Pad1)") (class "Default")
      (node (ref "R22") (pin "1") (pinfunction "1_1") (pintype "passive"))
      (node (ref "R24") (pin "2") (pinfunction "2_2") (pintype "passive"))
    )
    (net (code "29") (name "Net-(U3-AINN)") (class "Default")
      (node (ref "C8") (pin "2") (pinfunction "2_2") (pintype "passive"))
      (node (ref "R4") (pin "2") (pinfunction "2_2") (pintype "passive"))
      (node (ref "U3") (pin "3") (pinfunction "AINN_3") (pintype "input"))
    )
    (net (code "30") (name "Net-(U3-AINP)") (class "Default")
      (node (ref "C8") (pin "1") (pinfunction "1_1") (pintype "passive"))
      (node (ref "R2") (pin "2") (pinfunction "2_2") (pintype "passive"))
      (node (ref "U3") (pin "2") (pinfunction "AINP_2") (pintype "input"))
    )
    (net (code "31") (name "Net-(U3-CLKOUT)") (class "Default")
      (node (ref "R3") (pin "1") (pinfunction "1_1") (pintype "passive"))
      (node (ref "U3") (pin "7") (pinfunction "CLKOUT_7") (pintype "passive"))
    )
    (net (code "32") (name "Net-(U3-DOUT)") (class "Default")
      (node (ref "R1") (pin "1") (pinfunction "1_1") (pintype "passive"))
      (node (ref "U3") (pin "6") (pinfunction "DOUT_6") (pintype "output"))
    )
    (net (code "33") (name "Net-(U5-AINN)") (class "Default")
      (node (ref "C16") (pin "2") (pinfunction "2_2") (pintype "passive"))
      (node (ref "R8") (pin "2") (pinfunction "2_2") (pintype "passive"))
      (node (ref "U5") (pin "3") (pinfunction "AINN_3") (pintype "input"))
    )
    (net (code "34") (name "Net-(U5-AINP)") (class "Default")
      (node (ref "C16") (pin "1") (pinfunction "1_1") (pintype "passive"))
      (node (ref "R6") (pin "2") (pinfunction "2_2") (pintype "passive"))
      (node (ref "U5") (pin "2") (pinfunction "AINP_2") (pintype "input"))
    )
    (net (code "35") (name "Net-(U5-CLKOUT)") (class "Default")
      (node (ref "R7") (pin "1") (pinfunction "1_1") (pintype "passive"))
      (node (ref "U5") (pin "7") (pinfunction "CLKOUT_7") (pintype "passive"))
    )
    (net (code "36") (name "Net-(U5-DOUT)") (class "Default")
      (node (ref "R5") (pin "1") (pinfunction "1_1") (pintype "passive"))
      (node (ref "U5") (pin "6") (pinfunction "DOUT_6") (pintype "output"))
    )
    (net (code "37") (name "Net-(U7-AINN)") (class "Default")
      (node (ref "C52") (pin "2") (pinfunction "2_2") (pintype "passive"))
      (node (ref "R47") (pin "2") (pinfunction "2_2") (pintype "passive"))
      (node (ref "U7") (pin "3") (pinfunction "AINN_3") (pintype "input"))
    )
    (net (code "38") (name "Net-(U7-AINP)") (class "Default")
      (node (ref "C52") (pin "1") (pinfunction "1_1") (pintype "passive"))
      (node (ref "R46") (pin "2") (pinfunction "2_2") (pintype "passive"))
      (node (ref "U7") (pin "2") (pinfunction "AINP_2") (pintype "input"))
    )
    (net (code "39") (name "Net-(U7-CLKOUT)") (class "Default")
      (node (ref "R10") (pin "1") (pinfunction "1_1") (pintype "passive"))
      (node (ref "U7") (pin "7") (pinfunction "CLKOUT_7") (pintype "passive"))
    )
    (net (code "40") (name "Net-(U7-DOUT)") (class "Default")
      (node (ref "R9") (pin "1") (pinfunction "1_1") (pintype "passive"))
      (node (ref "U7") (pin "6") (pinfunction "DOUT_6") (pintype "output"))
    )
    (net (code "41") (name "Net-(U9-CFO)") (class "Default")
      (node (ref "C43") (pin "2") (pinfunction "2_2") (pintype "passive"))
      (node (ref "U9") (pin "25") (pinfunction "CFO_25") (pintype "passive"))
    )
    (net (code "42") (name "Net-(U9-CIN)") (class "Default")
      (node (ref "C44") (pin "1") (pinfunction "1_1") (pintype "passive"))
      (node (ref "R28") (pin "1") (pinfunction "1_1") (pintype "passive"))
      (node (ref "U9") (pin "24") (pinfunction "CIN_24") (pintype "passive"))
    )
    (net (code "43") (name "Net-(U9-UN)") (class "Default")
      (node (ref "C27") (pin "1") (pinfunction "1_1") (pintype "passive"))
      (node (ref "R21") (pin "2") (pinfunction "2_2") (pintype "passive"))
      (node (ref "U9") (pin "27") (pinfunction "UN_27") (pintype "passive"))
    )
    (net (code "44") (name "Net-(U9-UP)") (class "Default")
      (node (ref "C23") (pin "1") (pinfunction "1_1") (pintype "passive"))
      (node (ref "R12") (pin "2") (pinfunction "2_2") (pintype "passive"))
      (node (ref "U9") (pin "1") (pinfunction "UP_1") (pintype "passive"))
    )
    (net (code "45") (name "Net-(U9-VN)") (class "Default")
      (node (ref "C28") (pin "1") (pinfunction "1_1") (pintype "passive"))
      (node (ref "R23") (pin "2") (pinfunction "2_2") (pintype "passive"))
      (node (ref "U9") (pin "28") (pinfunction "VN_28") (pintype "passive"))
    )
    (net (code "46") (name "Net-(U9-VP)") (class "Default")
      (node (ref "C24") (pin "1") (pinfunction "1_1") (pintype "passive"))
      (node (ref "R15") (pin "2") (pinfunction "2_2") (pintype "passive"))
      (node (ref "U9") (pin "7") (pinfunction "VP_7") (pintype "passive"))
    )
    (net (code "47") (name "Net-(U9-VSC)") (class "Default")
      (node (ref "R28") (pin "2") (pinfunction "2_2") (pintype "passive"))
      (node (ref "R29") (pin "1") (pinfunction "1_1") (pintype "passive"))
      (node (ref "U9") (pin "19") (pinfunction "VSC_19") (pintype "passive"))
    )
    (net (code "48") (name "Net-(U9-WN)") (class "Default")
      (node (ref "C29") (pin "1") (pinfunction "1_1") (pintype "passive"))
      (node (ref "R25") (pin "2") (pinfunction "2_2") (pintype "passive"))
      (node (ref "U9") (pin "29") (pinfunction "WN_29") (pintype "passive"))
    )
    (net (code "49") (name "Net-(U9-WP)") (class "Default")
      (node (ref "C25") (pin "1") (pinfunction "1_1") (pintype "passive"))
      (node (ref "R17") (pin "2") (pinfunction "2_2") (pintype "passive"))
      (node (ref "U9") (pin "13") (pinfunction "WP_13") (pintype "passive"))
    )
    (net (code "50") (name "P15V") (class "Default")
      (node (ref "C30") (pin "1") (pinfunction "1_1") (pintype "passive"))
      (node (ref "C33") (pin "1") (pinfunction "1_1") (pintype "passive"))
      (node (ref "C34") (pin "1") (pinfunction "1_1") (pintype "passive"))
      (node (ref "C37") (pin "1") (pinfunction "1_1") (pintype "passive"))
      (node (ref "C38") (pin "1") (pinfunction "1_1") (pintype "passive"))
      (node (ref "D3") (pin "1") (pinfunction "K_1") (pintype "passive"))
      (node (ref "U9") (pin "14") (pinfunction "VP1_14") (pintype "passive"))
      (node (ref "U9") (pin "21") (pinfunction "VN1_21") (pintype "passive"))
      (node (ref "U9") (pin "3") (pinfunction "VP1_3") (pintype "passive"))
      (node (ref "U9") (pin "9") (pinfunction "VP1_9") (pintype "passive"))
    )
    (net (code "51") (name "PH_U") (class "Default")
      (node (ref "J5") (pin "2") (pinfunction "2_2") (pintype "passive"))
      (node (ref "R18") (pin "2") (pinfunction "2_2") (pintype "passive"))
      (node (ref "R2") (pin "1") (pinfunction "1_1") (pintype "passive"))
    )
    (net (code "52") (name "PH_V") (class "Default")
      (node (ref "J5") (pin "1") (pinfunction "1_1") (pintype "passive"))
      (node (ref "R19") (pin "2") (pinfunction "2_2") (pintype "passive"))
      (node (ref "R6") (pin "1") (pinfunction "1_1") (pintype "passive"))
    )
    (net (code "53") (name "PWM_U_B_IPM") (class "Default")
      (node (ref "R21") (pin "1") (pinfunction "1_1") (pintype "passive"))
    )
    (net (code "54") (name "PWM_U_T_IPM") (class "Default")
      (node (ref "R12") (pin "1") (pinfunction "1_1") (pintype "passive"))
    )
    (net (code "55") (name "PWM_V_B_IPM") (class "Default")
      (node (ref "R23") (pin "1") (pinfunction "1_1") (pintype "passive"))
    )
    (net (code "56") (name "PWM_V_T_IPM") (class "Default")
      (node (ref "R15") (pin "1") (pinfunction "1_1") (pintype "passive"))
    )
    (net (code "57") (name "PWM_W_B_IPM") (class "Default")
      (node (ref "R25") (pin "1") (pinfunction "1_1") (pintype "passive"))
    )
    (net (code "58") (name "PWM_W_T_IPM") (class "Default")
      (node (ref "R17") (pin "1") (pinfunction "1_1") (pintype "passive"))
    )
    (net (code "59") (name "VCC_PH_U") (class "Default")
      (node (ref "C39") (pin "1") (pinfunction "1_1") (pintype "passive"))
      (node (ref "C40") (pin "1") (pinfunction "1_1") (pintype "passive"))
      (node (ref "C7") (pin "2") (pinfunction "2_2") (pintype "passive"))
      (node (ref "D4") (pin "1") (pinfunction "K_1") (pintype "passive"))
      (node (ref "U2") (pin "2") (pinfunction "IN_2") (pintype "power_in"))
      (node (ref "U9") (pin "4") (pinfunction "VUFP_4") (pintype "passive"))
    )
    (net (code "60") (name "VCC_PH_V") (class "Default")
      (node (ref "C14") (pin "2") (pinfunction "2_2") (pintype "passive"))
      (node (ref "C35") (pin "1") (pinfunction "1_1") (pintype "passive"))
      (node (ref "C36") (pin "1") (pinfunction "1_1") (pintype "passive"))
      (node (ref "D2") (pin "1") (pinfunction "K_1") (pintype "passive"))
      (node (ref "U4") (pin "2") (pinfunction "IN_2") (pintype "power_in"))
      (node (ref "U9") (pin "10") (pinfunction "VVFB_10") (pintype "passive"))
    )
    (net (code "61") (name "V_DC_bus") (class "Default")
      (node (ref "R24") (pin "1") (pinfunction "1_1") (pintype "passive"))
      (node (ref "R26") (pin "2") (pinfunction "2_2") (pintype "passive"))
      (node (ref "R47") (pin "1") (pinfunction "1_1") (pintype "passive"))
    )
    (net (code "62") (name "unconnected-(J6-Pad1)") (class "Default")
      (node (ref "J6") (pin "1") (pinfunction "1_1") (pintype "passive+no_connect"))
    )
  )
)
